# TestA.net
KiCad netlist of a schematic drawn in EAGLE
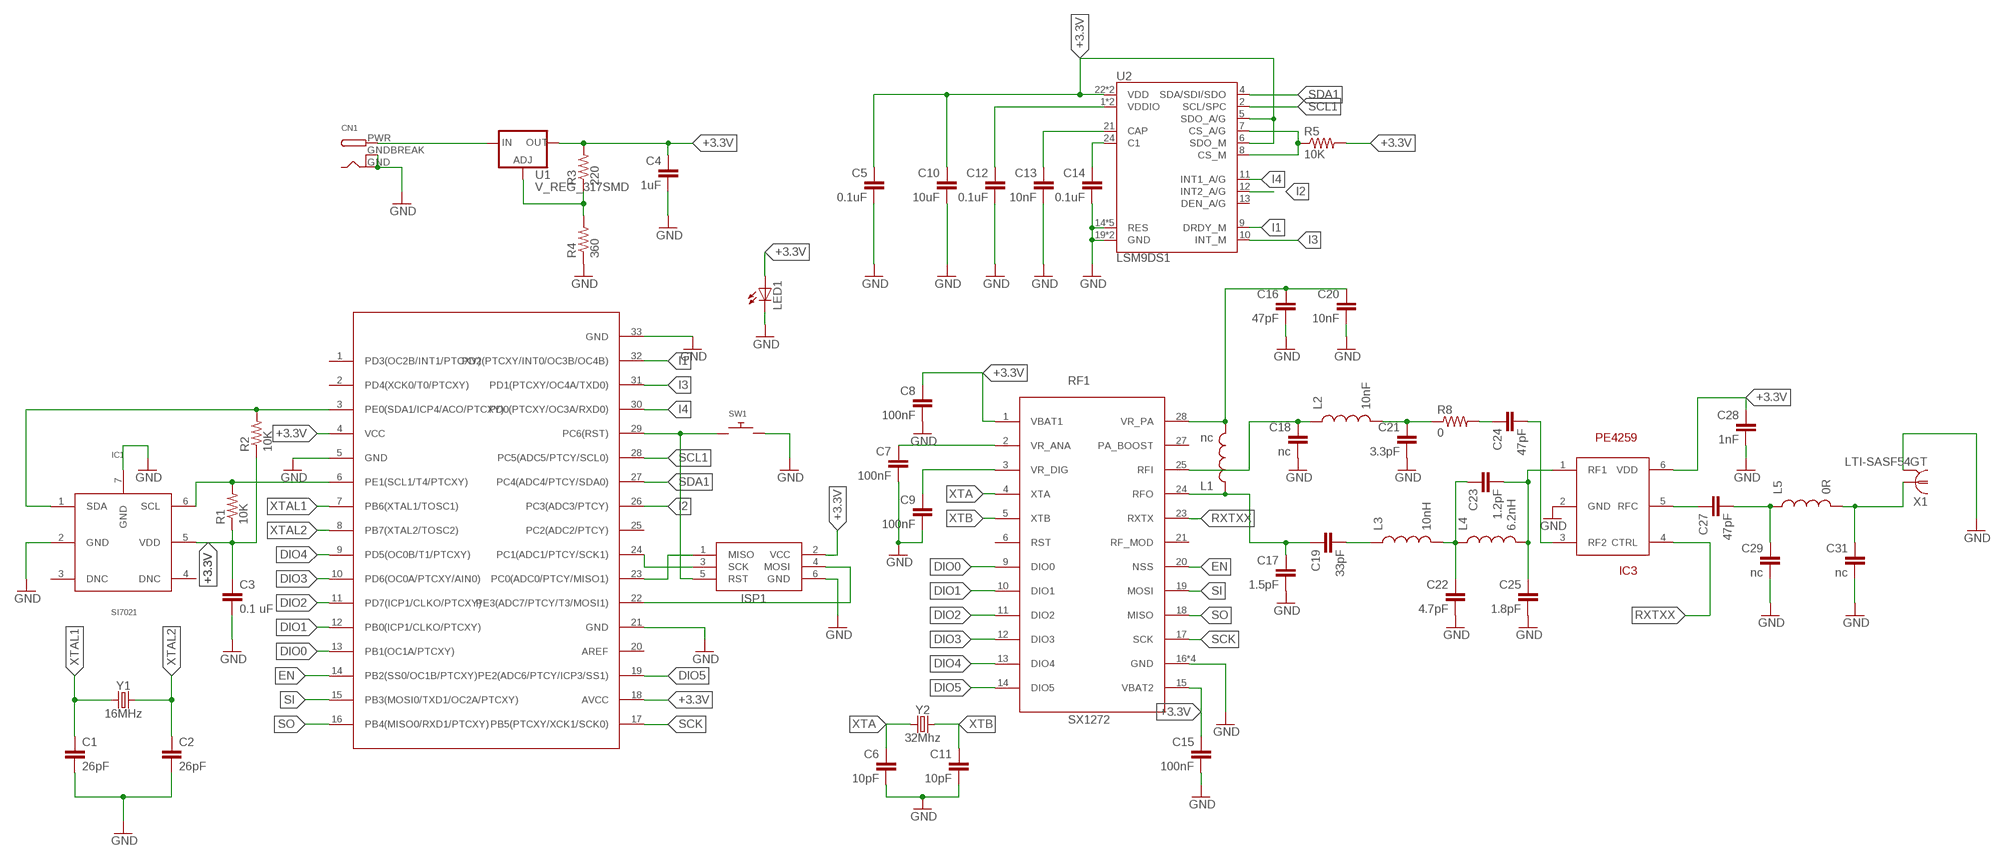
[diagram p0: schematic, sheet 1]

(export (version "E")
  (design (tool "Eeschema 10.0.6"))
  (components
    (comp (ref "C1")
      (value "26pF")
      (footprint "eagle-import:0402-CAP")
      (libsource (lib "eagle-import") (part "CAP0402-CAP"))
    )
    (comp (ref "C2")
      (value "26pF")
      (footprint "eagle-import:0402-CAP")
      (libsource (lib "eagle-import") (part "CAP0402-CAP"))
    )
    (comp (ref "C3")
      (value "0.1 uF")
      (footprint "eagle-import:0402-CAP")
      (libsource (lib "eagle-import") (part "CAP0402-CAP"))
    )
    (comp (ref "C4")
      (value "1uF")
      (footprint "eagle-import:0402-CAP")
      (libsource (lib "eagle-import") (part "CAP0402-CAP"))
    )
    (comp (ref "C5")
      (value "0.1uF")
      (footprint "eagle-import:0402-CAP")
      (libsource (lib "eagle-import") (part "CAP0402-CAP"))
    )
    (comp (ref "C6")
      (value "10pF")
      (footprint "eagle-import:0402-CAP")
      (libsource (lib "eagle-import") (part "CAP0402-CAP"))
    )
    (comp (ref "C7")
      (value "100nF")
      (footprint "eagle-import:0402-CAP")
      (libsource (lib "eagle-import") (part "CAP0402-CAP"))
    )
    (comp (ref "C8")
      (value "100nF")
      (footprint "eagle-import:0402-CAP")
      (libsource (lib "eagle-import") (part "CAP0402-CAP"))
    )
    (comp (ref "C9")
      (value "100nF")
      (footprint "eagle-import:0402-CAP")
      (libsource (lib "eagle-import") (part "CAP0402-CAP"))
    )
    (comp (ref "C10")
      (value "10uF")
      (footprint "eagle-import:0402-CAP")
      (libsource (lib "eagle-import") (part "CAP0402-CAP"))
    )
    (comp (ref "C11")
      (value "10pF")
      (footprint "eagle-import:0402-CAP")
      (libsource (lib "eagle-import") (part "CAP0402-CAP"))
    )
    (comp (ref "C12")
      (value "0.1uF")
      (footprint "eagle-import:0402-CAP")
      (libsource (lib "eagle-import") (part "CAP0402-CAP"))
    )
    (comp (ref "C13")
      (value "10nF")
      (footprint "eagle-import:0402-CAP")
      (libsource (lib "eagle-import") (part "CAP0402-CAP"))
    )
    (comp (ref "C14")
      (value "0.1uF")
      (footprint "eagle-import:0402-CAP")
      (libsource (lib "eagle-import") (part "CAP0402-CAP"))
    )
    (comp (ref "C15")
      (value "100nF")
      (footprint "eagle-import:0402-CAP")
      (libsource (lib "eagle-import") (part "CAP0402-CAP"))
    )
    (comp (ref "C16")
      (value "47pF")
      (footprint "eagle-import:0402-CAP")
      (libsource (lib "eagle-import") (part "CAP0402-CAP"))
    )
    (comp (ref "C17")
      (value "1.5pF")
      (footprint "eagle-import:0402-CAP")
      (libsource (lib "eagle-import") (part "CAP0402-CAP"))
    )
    (comp (ref "C18")
      (value "nc")
      (footprint "eagle-import:0402-CAP")
      (libsource (lib "eagle-import") (part "CAP0402-CAP"))
    )
    (comp (ref "C19")
      (value "33pF")
      (footprint "eagle-import:0402-CAP")
      (libsource (lib "eagle-import") (part "CAP0402-CAP"))
    )
    (comp (ref "C20")
      (value "10nF")
      (footprint "eagle-import:0402-CAP")
      (libsource (lib "eagle-import") (part "CAP0402-CAP"))
    )
    (comp (ref "C21")
      (value "3.3pF")
      (footprint "eagle-import:0402-CAP")
      (libsource (lib "eagle-import") (part "CAP0402-CAP"))
    )
    (comp (ref "C22")
      (value "4.7pF")
      (footprint "eagle-import:0402-CAP")
      (libsource (lib "eagle-import") (part "CAP0402-CAP"))
    )
    (comp (ref "C23")
      (value "1.2pF")
      (footprint "eagle-import:0402-CAP")
      (libsource (lib "eagle-import") (part "CAP0402-CAP"))
    )
    (comp (ref "C24")
      (value "47pF")
      (footprint "eagle-import:0402-CAP")
      (libsource (lib "eagle-import") (part "CAP0402-CAP"))
    )
    (comp (ref "C25")
      (value "1.8pF")
      (footprint "eagle-import:0402-CAP")
      (libsource (lib "eagle-import") (part "CAP0402-CAP"))
    )
    (comp (ref "C27")
      (value "47pF")
      (footprint "eagle-import:0402-CAP")
      (libsource (lib "eagle-import") (part "CAP0402-CAP"))
    )
    (comp (ref "C28")
      (value "1nF")
      (footprint "eagle-import:0402-CAP")
      (libsource (lib "eagle-import") (part "CAP0402-CAP"))
    )
    (comp (ref "C29")
      (value "nc")
      (footprint "eagle-import:0402-CAP")
      (libsource (lib "eagle-import") (part "CAP0402-CAP"))
    )
    (comp (ref "C31")
      (value "nc")
      (footprint "eagle-import:0402-CAP")
      (libsource (lib "eagle-import") (part "CAP0402-CAP"))
    )
    (comp (ref "CN1")
      (value "DCBARRELPTH")
      (footprint "eagle-import:DCJACK_2MM_PTH")
      (libsource (lib "eagle-import") (part "DCBARRELPTH"))
    )
    (comp (ref "IC1")
      (value "SI7021")
      (footprint "eagle-import:SI7021")
      (libsource (lib "eagle-import") (part "SI7021"))
    )
    (comp (ref "IC2")
      (value "ATMEGA328-PB")
      (footprint "eagle-import:ATMEGA328-PB")
      (libsource (lib "eagle-import") (part "ATMEGA328-PB"))
    )
    (comp (ref "IC3")
      (value "PE4259")
      (footprint "eagle-import:PE4259")
      (libsource (lib "eagle-import") (part "PE4259"))
    )
    (comp (ref "ISP1")
      (value "AVRISP-6")
      (footprint "eagle-import:AVRISP")
      (libsource (lib "eagle-import") (part "AVRISP-6"))
    )
    (comp (ref "L1")
      (value "nc")
      (footprint "eagle-import:C0402")
      (libsource (lib "eagle-import") (part "INDUCTOR0402"))
    )
    (comp (ref "L2")
      (value "10nF")
      (footprint "eagle-import:C0402")
      (libsource (lib "eagle-import") (part "INDUCTOR0402"))
    )
    (comp (ref "L3")
      (value "10nH")
      (footprint "eagle-import:C0402")
      (libsource (lib "eagle-import") (part "INDUCTOR0402"))
    )
    (comp (ref "L4")
      (value "6.2nH")
      (footprint "eagle-import:C0402")
      (libsource (lib "eagle-import") (part "INDUCTOR0402"))
    )
    (comp (ref "L5")
      (value "0R")
      (footprint "eagle-import:C0402")
      (libsource (lib "eagle-import") (part "INDUCTOR0402"))
    )
    (comp (ref "LED1")
      (value "LED3MM")
      (footprint "eagle-import:LED3MM")
      (libsource (lib "eagle-import") (part "LED3MM"))
    )
    (comp (ref "R1")
      (value "10K")
      (footprint "eagle-import:0402-RES")
      (libsource (lib "eagle-import") (part "RESISTOR0402-RES"))
    )
    (comp (ref "R2")
      (value "10K")
      (footprint "eagle-import:0402-RES")
      (libsource (lib "eagle-import") (part "RESISTOR0402-RES"))
    )
    (comp (ref "R3")
      (value "220")
      (footprint "eagle-import:0402-RES")
      (libsource (lib "eagle-import") (part "RESISTOR0402-RES"))
    )
    (comp (ref "R4")
      (value "360")
      (footprint "eagle-import:0402-RES")
      (libsource (lib "eagle-import") (part "RESISTOR0402-RES"))
    )
    (comp (ref "R5")
      (value "10K")
      (footprint "eagle-import:0402-RES")
      (libsource (lib "eagle-import") (part "RESISTOR0402-RES"))
    )
    (comp (ref "R8")
      (value "0")
      (footprint "eagle-import:0402-RES")
      (libsource (lib "eagle-import") (part "RESISTOR0402-RES"))
    )
    (comp (ref "RF1")
      (value "SX1272")
      (footprint "eagle-import:SX1272")
      (libsource (lib "eagle-import") (part "SX1272"))
    )
    (comp (ref "SW1")
      (value "SWITCH_PUSHBUTTONSOFTTOUCHSMD_SJ")
      (footprint "eagle-import:PUSHBUTTON_SMD_SJ")
      (libsource (lib "eagle-import") (part "SWITCH_PUSHBUTTONSOFTTOUCHSMD_SJ"))
    )
    (comp (ref "U1")
      (value "V_REG_317SMD")
      (footprint "eagle-import:SOT223")
      (libsource (lib "eagle-import") (part "V_REG_317SMD"))
    )
    (comp (ref "U2")
      (value "LSM9DS1")
      (footprint "eagle-import:LGA24-8X4")
      (libsource (lib "eagle-import") (part "LSM9DS1"))
    )
    (comp (ref "X1")
      (value "LTI-SASF54GT")
      (footprint "eagle-import:LTI-SASF54GT")
      (libsource (lib "eagle-import") (part "LTI-SASF54GT"))
    )
    (comp (ref "Y1")
      (value "16MHz")
      (footprint "eagle-import:CRYSTAL-SMD-2.0X1.6MM")
      (libsource (lib "eagle-import") (part "CRYSTAL-16MHZSMD-2X1.6"))
    )
    (comp (ref "Y2")
      (value "32Mhz")
      (footprint "eagle-import:CRYSTAL-SMD-2.0X1.6MM")
      (libsource (lib "eagle-import") (part "CRYSTAL-16MHZSMD-2X1.6"))
    )
  )
  (nets
    (net (code "1") (name "+3.3V") (class "Default")
      (node (ref "C10") (pin "1") (pinfunction "1_1") (pintype "passive"))
      (node (ref "C15") (pin "1") (pinfunction "1_1") (pintype "passive"))
      (node (ref "C28") (pin "1") (pinfunction "1_1") (pintype "passive"))
      (node (ref "C3") (pin "1") (pinfunction "1_1") (pintype "passive"))
      (node (ref "C4") (pin "1") (pinfunction "1_1") (pintype "passive"))
      (node (ref "C5") (pin "1") (pinfunction "1_1") (pintype "passive"))
      (node (ref "C8") (pin "1") (pinfunction "1_1") (pintype "passive"))
      (node (ref "IC1") (pin "5") (pinfunction "VDD_5") (pintype "bidirectional"))
      (node (ref "IC2") (pin "18") (pinfunction "AVCC_18") (pintype "bidirectional"))
      (node (ref "IC2") (pin "4") (pinfunction "VCC_4") (pintype "bidirectional"))
      (node (ref "IC3") (pin "6") (pinfunction "VDD_6") (pintype "bidirectional"))
      (node (ref "ISP1") (pin "2") (pinfunction "VCC_2") (pintype "power_in"))
      (node (ref "LED1") (pin "A") (pinfunction "A_A") (pintype "passive"))
      (node (ref "R1") (pin "1") (pinfunction "1_1") (pintype "passive"))
      (node (ref "R2") (pin "1") (pinfunction "1_1") (pintype "passive"))
      (node (ref "R3") (pin "2") (pinfunction "2_2") (pintype "passive"))
      (node (ref "R5") (pin "2") (pinfunction "2_2") (pintype "passive"))
      (node (ref "RF1") (pin "1") (pinfunction "VBAT1_1") (pintype "bidirectional"))
      (node (ref "RF1") (pin "15") (pinfunction "VBAT2_15") (pintype "bidirectional"))
      (node (ref "U1") (pin "2") (pinfunction "OUT_2") (pintype "output"))
      (node (ref "U2") (pin "22") (pinfunction "VDD_22") (pintype "bidirectional"))
      (node (ref "U2") (pin "23") (pinfunction "VDD_23") (pintype "bidirectional"))
      (node (ref "U2") (pin "5") (pinfunction "SDO_A/G_5") (pintype "bidirectional"))
      (node (ref "U2") (pin "6") (pinfunction "SDO_M_6") (pintype "bidirectional"))
    )
    (net (code "2") (name "DIO0") (class "Default")
      (node (ref "IC2") (pin "13") (pinfunction "PB1(OC1A/PTCXY)_13") (pintype "bidirectional"))
      (node (ref "RF1") (pin "9") (pinfunction "DIO0_9") (pintype "bidirectional"))
    )
    (net (code "3") (name "DIO1") (class "Default")
      (node (ref "IC2") (pin "12") (pinfunction "PB0(ICP1/CLKO/PTCXY)_12") (pintype "bidirectional"))
      (node (ref "RF1") (pin "10") (pinfunction "DIO1_10") (pintype "bidirectional"))
    )
    (net (code "4") (name "DIO2") (class "Default")
      (node (ref "IC2") (pin "11") (pinfunction "PD7(ICP1/CLKO/PTCXY)_11") (pintype "bidirectional"))
      (node (ref "RF1") (pin "11") (pinfunction "DIO2_11") (pintype "bidirectional"))
    )
    (net (code "5") (name "DIO3") (class "Default")
      (node (ref "IC2") (pin "10") (pinfunction "PD6(OC0A/PTCXY/AIN0)_10") (pintype "bidirectional"))
      (node (ref "RF1") (pin "12") (pinfunction "DIO3_12") (pintype "bidirectional"))
    )
    (net (code "6") (name "DIO4") (class "Default")
      (node (ref "IC2") (pin "9") (pinfunction "PD5(OC0B/T1/PTCXY)_9") (pintype "bidirectional"))
      (node (ref "RF1") (pin "13") (pinfunction "DIO4_13") (pintype "bidirectional"))
    )
    (net (code "7") (name "DIO5") (class "Default")
      (node (ref "IC2") (pin "19") (pinfunction "PE2(ADC6/PTCY/ICP3/SS1)_19") (pintype "bidirectional"))
      (node (ref "RF1") (pin "14") (pinfunction "DIO5_14") (pintype "bidirectional"))
    )
    (net (code "8") (name "EN") (class "Default")
      (node (ref "IC2") (pin "14") (pinfunction "PB2(SS0/OC1B/PTCXY)_14") (pintype "bidirectional"))
      (node (ref "RF1") (pin "20") (pinfunction "NSS_20") (pintype "bidirectional"))
    )
    (net (code "9") (name "GND") (class "Default")
      (node (ref "C1") (pin "2") (pinfunction "2_2") (pintype "passive"))
      (node (ref "C10") (pin "2") (pinfunction "2_2") (pintype "passive"))
      (node (ref "C11") (pin "2") (pinfunction "2_2") (pintype "passive"))
      (node (ref "C12") (pin "2") (pinfunction "2_2") (pintype "passive"))
      (node (ref "C13") (pin "2") (pinfunction "2_2") (pintype "passive"))
      (node (ref "C14") (pin "2") (pinfunction "2_2") (pintype "passive"))
      (node (ref "C15") (pin "2") (pinfunction "2_2") (pintype "passive"))
      (node (ref "C16") (pin "2") (pinfunction "2_2") (pintype "passive"))
      (node (ref "C17") (pin "2") (pinfunction "2_2") (pintype "passive"))
      (node (ref "C18") (pin "2") (pinfunction "2_2") (pintype "passive"))
      (node (ref "C2") (pin "2") (pinfunction "2_2") (pintype "passive"))
      (node (ref "C20") (pin "2") (pinfunction "2_2") (pintype "passive"))
      (node (ref "C21") (pin "2") (pinfunction "2_2") (pintype "passive"))
      (node (ref "C22") (pin "2") (pinfunction "2_2") (pintype "passive"))
      (node (ref "C25") (pin "2") (pinfunction "2_2") (pintype "passive"))
      (node (ref "C28") (pin "2") (pinfunction "2_2") (pintype "passive"))
      (node (ref "C29") (pin "2") (pinfunction "2_2") (pintype "passive"))
      (node (ref "C3") (pin "2") (pinfunction "2_2") (pintype "passive"))
      (node (ref "C31") (pin "2") (pinfunction "2_2") (pintype "passive"))
      (node (ref "C4") (pin "2") (pinfunction "2_2") (pintype "passive"))
      (node (ref "C5") (pin "2") (pinfunction "2_2") (pintype "passive"))
      (node (ref "C6") (pin "2") (pinfunction "2_2") (pintype "passive"))
      (node (ref "C7") (pin "2") (pinfunction "2_2") (pintype "passive"))
      (node (ref "C8") (pin "2") (pinfunction "2_2") (pintype "passive"))
      (node (ref "C9") (pin "2") (pinfunction "2_2") (pintype "passive"))
      (node (ref "CN1") (pin "GND") (pinfunction "GND_GND") (pintype "power_in"))
      (node (ref "CN1") (pin "GNDBREAK") (pinfunction "GNDBREAK_GNDBREAK") (pintype "power_in"))
      (node (ref "IC1") (pin "2") (pinfunction "GND_2") (pintype "bidirectional"))
      (node (ref "IC1") (pin "7") (pinfunction "GND_7") (pintype "bidirectional"))
      (node (ref "IC2") (pin "21") (pinfunction "GND_21") (pintype "bidirectional"))
      (node (ref "IC2") (pin "33") (pinfunction "GND_33") (pintype "bidirectional"))
      (node (ref "IC2") (pin "5") (pinfunction "GND_5") (pintype "bidirectional"))
      (node (ref "IC3") (pin "2") (pinfunction "GND_2") (pintype "bidirectional"))
      (node (ref "ISP1") (pin "6") (pinfunction "GND_6") (pintype "power_in"))
      (node (ref "LED1") (pin "K") (pinfunction "C_K") (pintype "passive"))
      (node (ref "R4") (pin "1") (pinfunction "1_1") (pintype "passive"))
      (node (ref "RF1") (pin "16") (pinfunction "GND_16") (pintype "bidirectional"))
      (node (ref "RF1") (pin "22") (pinfunction "GND_22") (pintype "bidirectional"))
      (node (ref "RF1") (pin "26") (pinfunction "GND_26") (pintype "bidirectional"))
      (node (ref "RF1") (pin "29") (pinfunction "GND_29") (pintype "bidirectional"))
      (node (ref "SW1") (pin "P$2") (pinfunction "P$2_P$2") (pintype "passive"))
      (node (ref "U2") (pin "14") (pinfunction "RES_14") (pintype "bidirectional"))
      (node (ref "U2") (pin "15") (pinfunction "RES_15") (pintype "bidirectional"))
      (node (ref "U2") (pin "16") (pinfunction "RES_16") (pintype "bidirectional"))
      (node (ref "U2") (pin "17") (pinfunction "RES_17") (pintype "bidirectional"))
      (node (ref "U2") (pin "18") (pinfunction "RES_18") (pintype "bidirectional"))
      (node (ref "U2") (pin "19") (pinfunction "GND_19") (pintype "bidirectional"))
      (node (ref "U2") (pin "20") (pinfunction "GND_20") (pintype "bidirectional"))
      (node (ref "X1") (pin "2") (pinfunction "2_2") (pintype "passive"))
      (node (ref "X1") (pin "3") (pinfunction "2_3") (pintype "passive"))
      (node (ref "X1") (pin "4") (pinfunction "2_4") (pintype "passive"))
      (node (ref "X1") (pin "5") (pinfunction "2_5") (pintype "passive"))
    )
    (net (code "10") (name "I1") (class "Default")
      (node (ref "IC2") (pin "32") (pinfunction "PD2(PTCXY/INT0/OC3B/OC4B)_32") (pintype "bidirectional"))
      (node (ref "U2") (pin "9") (pinfunction "DRDY_M_9") (pintype "bidirectional"))
    )
    (net (code "11") (name "I2") (class "Default")
      (node (ref "IC2") (pin "26") (pinfunction "PC3(ADC3/PTCY)_26") (pintype "bidirectional"))
      (node (ref "U2") (pin "12") (pinfunction "INT2_A/G_12") (pintype "bidirectional"))
    )
    (net (code "12") (name "I3") (class "Default")
      (node (ref "IC2") (pin "31") (pinfunction "PD1(PTCXY/OC4A/TXD0)_31") (pintype "bidirectional"))
      (node (ref "U2") (pin "10") (pinfunction "INT_M_10") (pintype "bidirectional"))
    )
    (net (code "13") (name "I4") (class "Default")
      (node (ref "IC2") (pin "30") (pinfunction "PD0(PTCXY/OC3A/RXD0)_30") (pintype "bidirectional"))
      (node (ref "U2") (pin "11") (pinfunction "INT1_A/G_11") (pintype "bidirectional"))
    )
    (net (code "14") (name "Net-(C12-Pad1)") (class "Default")
      (node (ref "C12") (pin "1") (pinfunction "1_1") (pintype "passive"))
      (node (ref "U2") (pin "1") (pinfunction "VDDIO_1") (pintype "bidirectional"))
      (node (ref "U2") (pin "3") (pinfunction "VDDIO_3") (pintype "bidirectional"))
    )
    (net (code "15") (name "Net-(C19-Pad2)") (class "Default")
      (node (ref "C19") (pin "2") (pinfunction "2_2") (pintype "passive"))
      (node (ref "L3") (pin "1") (pinfunction "1_1") (pintype "passive"))
    )
    (net (code "16") (name "Net-(C21-Pad1)") (class "Default")
      (node (ref "C21") (pin "1") (pinfunction "1_1") (pintype "passive"))
      (node (ref "L2") (pin "2") (pinfunction "2_2") (pintype "passive"))
      (node (ref "R8") (pin "1") (pinfunction "1_1") (pintype "passive"))
    )
    (net (code "17") (name "Net-(C22-Pad1)") (class "Default")
      (node (ref "C22") (pin "1") (pinfunction "1_1") (pintype "passive"))
      (node (ref "C23") (pin "1") (pinfunction "1_1") (pintype "passive"))
      (node (ref "L3") (pin "2") (pinfunction "2_2") (pintype "passive"))
      (node (ref "L4") (pin "1") (pinfunction "1_1") (pintype "passive"))
    )
    (net (code "18") (name "Net-(C24-Pad1)") (class "Default")
      (node (ref "C24") (pin "1") (pinfunction "1_1") (pintype "passive"))
      (node (ref "R8") (pin "2") (pinfunction "2_2") (pintype "passive"))
    )
    (net (code "19") (name "Net-(C27-Pad2)") (class "Default")
      (node (ref "C27") (pin "2") (pinfunction "2_2") (pintype "passive"))
      (node (ref "C29") (pin "1") (pinfunction "1_1") (pintype "passive"))
      (node (ref "L5") (pin "1") (pinfunction "1_1") (pintype "passive"))
    )
    (net (code "20") (name "Net-(C31-Pad1)") (class "Default")
      (node (ref "C31") (pin "1") (pinfunction "1_1") (pintype "passive"))
      (node (ref "L5") (pin "2") (pinfunction "2_2") (pintype "passive"))
      (node (ref "X1") (pin "1") (pinfunction "1_1") (pintype "passive"))
    )
    (net (code "21") (name "Net-(IC1-SCL)") (class "Default")
      (node (ref "IC1") (pin "6") (pinfunction "SCL_6") (pintype "bidirectional"))
      (node (ref "IC2") (pin "6") (pinfunction "PE1(SCL1/T4/PTCXY)_6") (pintype "bidirectional"))
      (node (ref "R1") (pin "2") (pinfunction "2_2") (pintype "passive"))
    )
    (net (code "22") (name "Net-(IC1-SDA)") (class "Default")
      (node (ref "IC1") (pin "1") (pinfunction "SDA_1") (pintype "bidirectional"))
      (node (ref "IC2") (pin "3") (pinfunction "PE0(SDA1/ICP4/ACO/PTCXY)_3") (pintype "bidirectional"))
      (node (ref "R2") (pin "2") (pinfunction "2_2") (pintype "passive"))
    )
    (net (code "23") (name "Net-(IC2-PC0(ADC0{slash}PTCY{slash}MISO1))") (class "Default")
      (node (ref "IC2") (pin "23") (pinfunction "PC0(ADC0/PTCY/MISO1)_23") (pintype "bidirectional"))
      (node (ref "ISP1") (pin "1") (pinfunction "MISO_1") (pintype "input"))
    )
    (net (code "24") (name "Net-(IC2-PC1(ADC1{slash}PTCY{slash}SCK1))") (class "Default")
      (node (ref "IC2") (pin "24") (pinfunction "PC1(ADC1/PTCY/SCK1)_24") (pintype "bidirectional"))
      (node (ref "ISP1") (pin "3") (pinfunction "SCK_3") (pintype "output"))
    )
    (net (code "25") (name "Net-(IC2-PC6(RST))") (class "Default")
      (node (ref "IC2") (pin "29") (pinfunction "PC6(RST)_29") (pintype "bidirectional"))
      (node (ref "ISP1") (pin "5") (pinfunction "RST_5") (pintype "output"))
      (node (ref "SW1") (pin "P$1") (pinfunction "P$1_P$1") (pintype "passive"))
    )
    (net (code "26") (name "Net-(IC2-PE3(ADC7{slash}PTCY{slash}T3{slash}MOSI1))") (class "Default")
      (node (ref "IC2") (pin "22") (pinfunction "PE3(ADC7/PTCY/T3/MOSI1)_22") (pintype "bidirectional"))
      (node (ref "ISP1") (pin "4") (pinfunction "MOSI_4") (pintype "output"))
    )
    (net (code "27") (name "Net-(IC3-RF1)") (class "Default")
      (node (ref "C23") (pin "2") (pinfunction "2_2") (pintype "passive"))
      (node (ref "C25") (pin "1") (pinfunction "1_1") (pintype "passive"))
      (node (ref "IC3") (pin "1") (pinfunction "RF1_1") (pintype "bidirectional"))
      (node (ref "L4") (pin "2") (pinfunction "2_2") (pintype "passive"))
    )
    (net (code "28") (name "Net-(IC3-RF2)") (class "Default")
      (node (ref "C24") (pin "2") (pinfunction "2_2") (pintype "passive"))
      (node (ref "IC3") (pin "3") (pinfunction "RF2_3") (pintype "bidirectional"))
    )
    (net (code "29") (name "Net-(IC3-RFC)") (class "Default")
      (node (ref "C27") (pin "1") (pinfunction "1_1") (pintype "passive"))
      (node (ref "IC3") (pin "5") (pinfunction "RFC_5") (pintype "bidirectional"))
    )
    (net (code "30") (name "Net-(RF1-RFI)") (class "Default")
      (node (ref "C18") (pin "1") (pinfunction "1_1") (pintype "passive"))
      (node (ref "L2") (pin "1") (pinfunction "1_1") (pintype "passive"))
      (node (ref "RF1") (pin "25") (pinfunction "RFI_25") (pintype "bidirectional"))
    )
    (net (code "31") (name "Net-(RF1-RFO)") (class "Default")
      (node (ref "C17") (pin "1") (pinfunction "1_1") (pintype "passive"))
      (node (ref "C19") (pin "1") (pinfunction "1_1") (pintype "passive"))
      (node (ref "L1") (pin "1") (pinfunction "1_1") (pintype "passive"))
      (node (ref "RF1") (pin "24") (pinfunction "RFO_24") (pintype "bidirectional"))
    )
    (net (code "32") (name "Net-(RF1-VR_ANA)") (class "Default")
      (node (ref "C7") (pin "1") (pinfunction "1_1") (pintype "passive"))
      (node (ref "RF1") (pin "2") (pinfunction "VR_ANA_2") (pintype "bidirectional"))
    )
    (net (code "33") (name "Net-(RF1-VR_DIG)") (class "Default")
      (node (ref "C9") (pin "1") (pinfunction "1_1") (pintype "passive"))
      (node (ref "RF1") (pin "3") (pinfunction "VR_DIG_3") (pintype "bidirectional"))
    )
    (net (code "34") (name "Net-(RF1-VR_PA)") (class "Default")
      (node (ref "C16") (pin "1") (pinfunction "1_1") (pintype "passive"))
      (node (ref "C20") (pin "1") (pinfunction "1_1") (pintype "passive"))
      (node (ref "L1") (pin "2") (pinfunction "2_2") (pintype "passive"))
      (node (ref "RF1") (pin "28") (pinfunction "VR_PA_28") (pintype "bidirectional"))
    )
    (net (code "35") (name "Net-(U1-ADJ)") (class "Default")
      (node (ref "R3") (pin "1") (pinfunction "1_1") (pintype "passive"))
      (node (ref "R4") (pin "2") (pinfunction "2_2") (pintype "passive"))
      (node (ref "U1") (pin "1") (pinfunction "ADJ_1") (pintype "input"))
    )
    (net (code "36") (name "Net-(U1-IN)") (class "Default")
      (node (ref "CN1") (pin "PWR") (pinfunction "PWR_PWR") (pintype "power_in"))
      (node (ref "U1") (pin "3") (pinfunction "IN_3") (pintype "input"))
    )
    (net (code "37") (name "Net-(U2-C1)") (class "Default")
      (node (ref "C14") (pin "1") (pinfunction "1_1") (pintype "passive"))
      (node (ref "U2") (pin "24") (pinfunction "C1_24") (pintype "bidirectional"))
    )
    (net (code "38") (name "Net-(U2-CAP)") (class "Default")
      (node (ref "C13") (pin "1") (pinfunction "1_1") (pintype "passive"))
      (node (ref "U2") (pin "21") (pinfunction "CAP_21") (pintype "bidirectional"))
    )
    (net (code "39") (name "Net-(U2-CS_A{slash}G)") (class "Default")
      (node (ref "R5") (pin "1") (pinfunction "1_1") (pintype "passive"))
      (node (ref "U2") (pin "7") (pinfunction "CS_A/G_7") (pintype "bidirectional"))
      (node (ref "U2") (pin "8") (pinfunction "CS_M_8") (pintype "bidirectional"))
    )
    (net (code "40") (name "RXTXX") (class "Default")
      (node (ref "IC3") (pin "4") (pinfunction "CTRL_4") (pintype "bidirectional"))
      (node (ref "RF1") (pin "23") (pinfunction "RXTX_23") (pintype "bidirectional"))
    )
    (net (code "41") (name "SCK") (class "Default")
      (node (ref "IC2") (pin "17") (pinfunction "PB5(PTCXY/XCK1/SCK0)_17") (pintype "bidirectional"))
      (node (ref "RF1") (pin "17") (pinfunction "SCK_17") (pintype "bidirectional"))
    )
    (net (code "42") (name "SCL1") (class "Default")
      (node (ref "IC2") (pin "28") (pinfunction "PC5(ADC5/PTCY/SCL0)_28") (pintype "bidirectional"))
      (node (ref "U2") (pin "2") (pinfunction "SCL/SPC_2") (pintype "bidirectional"))
    )
    (net (code "43") (name "SDA1") (class "Default")
      (node (ref "IC2") (pin "27") (pinfunction "PC4(ADC4/PTCY/SDA0)_27") (pintype "bidirectional"))
      (node (ref "U2") (pin "4") (pinfunction "SDA/SDI/SDO_4") (pintype "bidirectional"))
    )
    (net (code "44") (name "SI") (class "Default")
      (node (ref "IC2") (pin "15") (pinfunction "PB3(MOSI0/TXD1/OC2A/PTCXY)_15") (pintype "bidirectional"))
      (node (ref "RF1") (pin "19") (pinfunction "MOSI_19") (pintype "bidirectional"))
    )
    (net (code "45") (name "SO") (class "Default")
      (node (ref "IC2") (pin "16") (pinfunction "PB4(MISO0/RXD1/PTCXY)_16") (pintype "bidirectional"))
      (node (ref "RF1") (pin "18") (pinfunction "MISO_18") (pintype "bidirectional"))
    )
    (net (code "46") (name "XTA") (class "Default")
      (node (ref "C6") (pin "1") (pinfunction "1_1") (pintype "passive"))
      (node (ref "RF1") (pin "4") (pinfunction "XTA_4") (pintype "bidirectional"))
      (node (ref "Y2") (pin "1") (pinfunction "1_1") (pintype "passive"))
    )
    (net (code "47") (name "XTAL1") (class "Default")
      (node (ref "C1") (pin "1") (pinfunction "1_1") (pintype "passive"))
      (node (ref "IC2") (pin "7") (pinfunction "PB6(XTAL1/TOSC1)_7") (pintype "bidirectional"))
      (node (ref "Y1") (pin "1") (pinfunction "1_1") (pintype "passive"))
    )
    (net (code "48") (name "XTAL2") (class "Default")
      (node (ref "C2") (pin "1") (pinfunction "1_1") (pintype "passive"))
      (node (ref "IC2") (pin "8") (pinfunction "PB7(XTAL2/TOSC2)_8") (pintype "bidirectional"))
      (node (ref "Y1") (pin "3") (pinfunction "2_3") (pintype "passive"))
    )
    (net (code "49") (name "XTB") (class "Default")
      (node (ref "C11") (pin "1") (pinfunction "1_1") (pintype "passive"))
      (node (ref "RF1") (pin "5") (pinfunction "XTB_5") (pintype "bidirectional"))
      (node (ref "Y2") (pin "3") (pinfunction "2_3") (pintype "passive"))
    )
    (net (code "50") (name "unconnected-(IC1-DNC-Pad3)") (class "Default")
      (node (ref "IC1") (pin "3") (pinfunction "DNC_3") (pintype "bidirectional"))
    )
    (net (code "51") (name "unconnected-(IC1-DNC-Pad4)") (class "Default")
      (node (ref "IC1") (pin "4") (pinfunction "DNC_4") (pintype "bidirectional"))
    )
    (net (code "52") (name "unconnected-(IC2-AREF-Pad20)") (class "Default")
      (node (ref "IC2") (pin "20") (pinfunction "AREF_20") (pintype "bidirectional"))
    )
    (net (code "53") (name "unconnected-(IC2-PC2(ADC2{slash}PTCY)-Pad25)") (class "Default")
      (node (ref "IC2") (pin "25") (pinfunction "PC2(ADC2/PTCY)_25") (pintype "bidirectional"))
    )
    (net (code "54") (name "unconnected-(IC2-PD3(OC2B{slash}INT1{slash}PTCXY)-Pad1)") (class "Default")
      (node (ref "IC2") (pin "1") (pinfunction "PD3(OC2B/INT1/PTCXY)_1") (pintype "bidirectional"))
    )
    (net (code "55") (name "unconnected-(IC2-PD4(XCK0{slash}T0{slash}PTCXY)-Pad2)") (class "Default")
      (node (ref "IC2") (pin "2") (pinfunction "PD4(XCK0/T0/PTCXY)_2") (pintype "bidirectional"))
    )
    (net (code "56") (name "unconnected-(RF1-PA_BOOST-Pad27)") (class "Default")
      (node (ref "RF1") (pin "27") (pinfunction "PA_BOOST_27") (pintype "bidirectional"))
    )
    (net (code "57") (name "unconnected-(RF1-RF_MOD-Pad21)") (class "Default")
      (node (ref "RF1") (pin "21") (pinfunction "RF_MOD_21") (pintype "bidirectional"))
    )
    (net (code "58") (name "unconnected-(RF1-RST-Pad6)") (class "Default")
      (node (ref "RF1") (pin "6") (pinfunction "RST_6") (pintype "bidirectional"))
    )
    (net (code "59") (name "unconnected-(U2-DEN_A{slash}G-Pad13)") (class "Default")
      (node (ref "U2") (pin "13") (pinfunction "DEN_A/G_13") (pintype "bidirectional"))
    )
  )
)
